# VIA_MOTORS.net
KiCad netlist of a schematic drawn in Altium Designer
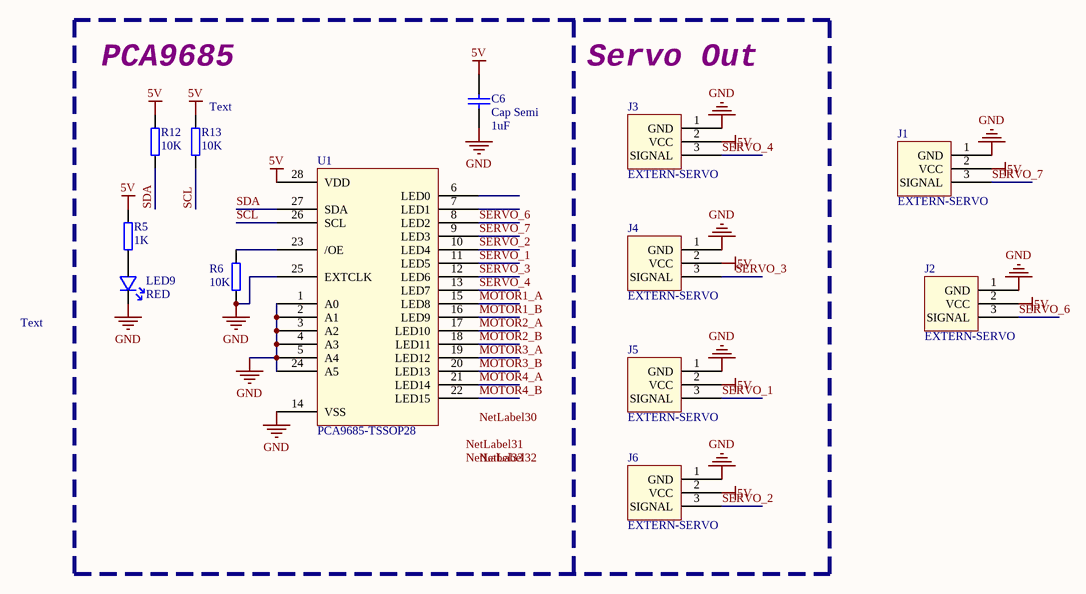
[diagram p0: VIA_MOTORS.SchDoc]

(export (version "E")
  (design (tool "Eeschema 10.0.6"))
  (components
    (comp (ref "C6")
      (value "Cap Semi")
      (footprint "SMT0603")
      (description "CAP SM 0603 X7R 1uF 10%")
      (fields (field (name "TOLERANCE") "±10%") (field (name "ALTIUM_VALUE") "1uF"))
      (libsource (lib "electronpowered") (part "CAP-SM-0603-X7R-1uF"))
    )
    (comp (ref "J1")
      (value "EXTERN-SERVO")
      (footprint "JP3H")
      (libsource (lib "RASHBERRY_EXTERN") (part "EXTERN-SERVO"))
    )
    (comp (ref "J2")
      (value "EXTERN-SERVO")
      (footprint "JP3H")
      (libsource (lib "RASHBERRY_EXTERN") (part "EXTERN-SERVO"))
    )
    (comp (ref "J3")
      (value "EXTERN-SERVO")
      (footprint "JP3H")
      (libsource (lib "RASHBERRY_EXTERN") (part "EXTERN-SERVO"))
    )
    (comp (ref "J4")
      (value "EXTERN-SERVO")
      (footprint "JP3H")
      (libsource (lib "RASHBERRY_EXTERN") (part "EXTERN-SERVO"))
    )
    (comp (ref "J5")
      (value "EXTERN-SERVO")
      (footprint "JP3H")
      (libsource (lib "RASHBERRY_EXTERN") (part "EXTERN-SERVO"))
    )
    (comp (ref "J6")
      (value "EXTERN-SERVO")
      (footprint "JP3H")
      (libsource (lib "RASHBERRY_EXTERN") (part "EXTERN-SERVO"))
    )
    (comp (ref "LED9")
      (value "RED")
      (footprint "SMT0603P")
      (description "LED SM 0603 RED 1V95 FWD VOLTAGE")
      (libsource (lib "electronpowered") (part "LNJ237W82RA"))
    )
    (comp (ref "R5")
      (value "1K")
      (footprint "SMT0603")
      (description "RES SM 0603 1K")
      (fields (field (name "Comment") "Resistor"))
      (libsource (lib "electronpowered") (part "RES-SM-0603-1K"))
    )
    (comp (ref "R6")
      (value "10K")
      (footprint "SMT0603")
      (description "RES SM 0603 10K")
      (fields (field (name "Comment") "Resistor"))
      (libsource (lib "electronpowered") (part "RES-SM-0603-10K"))
    )
    (comp (ref "R12")
      (value "10K")
      (footprint "SMT0603")
      (description "RES SM 0603 10K")
      (fields (field (name "Comment") "Resistor"))
      (libsource (lib "electronpowered") (part "RES-SM-0603-10K"))
    )
    (comp (ref "R13")
      (value "10K")
      (footprint "SMT0603")
      (description "RES SM 0603 10K")
      (fields (field (name "Comment") "Resistor"))
      (libsource (lib "electronpowered") (part "RES-SM-0603-10K"))
    )
    (comp (ref "U1")
      (value "PCA9685-TSSOP28")
      (footprint "TSSOP28-SMD")
      (libsource (lib "RASHBERRY_EXTERN") (part "PCA9685-TSSOP28"))
    )
  )
  (nets
    (net (code "1") (name "/MOTOR1_A") (class "Default")
      (node (ref "U1") (pin "15") (pinfunction "LED8_15") (pintype "passive"))
    )
    (net (code "2") (name "/MOTOR1_B") (class "Default")
      (node (ref "U1") (pin "16") (pinfunction "LED9_16") (pintype "passive"))
    )
    (net (code "3") (name "/MOTOR2_A") (class "Default")
      (node (ref "U1") (pin "17") (pinfunction "LED10_17") (pintype "passive"))
    )
    (net (code "4") (name "/MOTOR2_B") (class "Default")
      (node (ref "U1") (pin "18") (pinfunction "LED11_18") (pintype "passive"))
    )
    (net (code "5") (name "/MOTOR3_A") (class "Default")
      (node (ref "U1") (pin "19") (pinfunction "LED12_19") (pintype "passive"))
    )
    (net (code "6") (name "/MOTOR3_B") (class "Default")
      (node (ref "U1") (pin "20") (pinfunction "LED13_20") (pintype "passive"))
    )
    (net (code "7") (name "/MOTOR4_A") (class "Default")
      (node (ref "U1") (pin "21") (pinfunction "LED14_21") (pintype "passive"))
    )
    (net (code "8") (name "/MOTOR4_B") (class "Default")
      (node (ref "U1") (pin "22") (pinfunction "LED15_22") (pintype "passive"))
    )
    (net (code "13") (name "/SCL") (class "Default")
      (node (ref "R13") (pin "1") (pinfunction "1_1") (pintype "passive"))
      (node (ref "U1") (pin "26") (pinfunction "SCL_26") (pintype "passive"))
    )
    (net (code "14") (name "/SDA") (class "Default")
      (node (ref "R12") (pin "1") (pinfunction "1_1") (pintype "passive"))
      (node (ref "U1") (pin "27") (pinfunction "SDA_27") (pintype "passive"))
    )
    (net (code "15") (name "/SERVO_1") (class "Default")
      (node (ref "J5") (pin "3") (pinfunction "SIGNAL_3") (pintype "passive"))
      (node (ref "U1") (pin "11") (pinfunction "LED5_11") (pintype "passive"))
    )
    (net (code "16") (name "/SERVO_2") (class "Default")
      (node (ref "J6") (pin "3") (pinfunction "SIGNAL_3") (pintype "passive"))
      (node (ref "U1") (pin "10") (pinfunction "LED4_10") (pintype "passive"))
    )
    (net (code "17") (name "/SERVO_3") (class "Default")
      (node (ref "J4") (pin "3") (pinfunction "SIGNAL_3") (pintype "passive"))
      (node (ref "U1") (pin "12") (pinfunction "LED6_12") (pintype "passive"))
    )
    (net (code "18") (name "/SERVO_4") (class "Default")
      (node (ref "J3") (pin "3") (pinfunction "SIGNAL_3") (pintype "passive"))
      (node (ref "U1") (pin "13") (pinfunction "LED7_13") (pintype "passive"))
    )
    (net (code "19") (name "/SERVO_6") (class "Default")
      (node (ref "J2") (pin "3") (pinfunction "SIGNAL_3") (pintype "passive"))
      (node (ref "U1") (pin "8") (pinfunction "LED2_8") (pintype "passive"))
    )
    (net (code "20") (name "/SERVO_7") (class "Default")
      (node (ref "J1") (pin "3") (pinfunction "SIGNAL_3") (pintype "passive"))
      (node (ref "U1") (pin "9") (pinfunction "LED3_9") (pintype "passive"))
    )
    (net (code "21") (name "5V") (class "Default")
      (node (ref "C6") (pin "2") (pinfunction "2_2") (pintype "passive"))
      (node (ref "J1") (pin "2") (pinfunction "VCC_2") (pintype "passive"))
      (node (ref "J2") (pin "2") (pinfunction "VCC_2") (pintype "passive"))
      (node (ref "J3") (pin "2") (pinfunction "VCC_2") (pintype "passive"))
      (node (ref "J4") (pin "2") (pinfunction "VCC_2") (pintype "passive"))
      (node (ref "J5") (pin "2") (pinfunction "VCC_2") (pintype "passive"))
      (node (ref "J6") (pin "2") (pinfunction "VCC_2") (pintype "passive"))
      (node (ref "R12") (pin "2") (pinfunction "2_2") (pintype "passive"))
      (node (ref "R13") (pin "2") (pinfunction "2_2") (pintype "passive"))
      (node (ref "R5") (pin "2") (pinfunction "2_2") (pintype "passive"))
      (node (ref "U1") (pin "28") (pinfunction "VDD_28") (pintype "passive"))
    )
    (net (code "22") (name "GND") (class "Default")
      (node (ref "C6") (pin "1") (pinfunction "1_1") (pintype "passive"))
      (node (ref "J1") (pin "1") (pinfunction "GND_1") (pintype "passive"))
      (node (ref "J2") (pin "1") (pinfunction "GND_1") (pintype "passive"))
      (node (ref "J3") (pin "1") (pinfunction "GND_1") (pintype "passive"))
      (node (ref "J4") (pin "1") (pinfunction "GND_1") (pintype "passive"))
      (node (ref "J5") (pin "1") (pinfunction "GND_1") (pintype "passive"))
      (node (ref "J6") (pin "1") (pinfunction "GND_1") (pintype "passive"))
      (node (ref "LED9") (pin "2") (pinfunction "2_2") (pintype "passive"))
      (node (ref "R6") (pin "1") (pinfunction "1_1") (pintype "passive"))
      (node (ref "U1") (pin "1") (pinfunction "A0_1") (pintype "passive"))
      (node (ref "U1") (pin "14") (pinfunction "VSS_14") (pintype "passive"))
      (node (ref "U1") (pin "2") (pinfunction "A1_2") (pintype "passive"))
      (node (ref "U1") (pin "24") (pinfunction "A5_24") (pintype "passive"))
      (node (ref "U1") (pin "25") (pinfunction "EXTCLK_25") (pintype "passive"))
      (node (ref "U1") (pin "3") (pinfunction "A2_3") (pintype "passive"))
      (node (ref "U1") (pin "4") (pinfunction "A3_4") (pintype "passive"))
      (node (ref "U1") (pin "5") (pinfunction "A4_5") (pintype "passive"))
    )
    (net (code "23") (name "Net-(LED9-Pad1)") (class "Default")
      (node (ref "LED9") (pin "1") (pinfunction "1_1") (pintype "passive"))
      (node (ref "R5") (pin "1") (pinfunction "1_1") (pintype "passive"))
    )
    (net (code "24") (name "Net-(U1-{slash}OE)") (class "Default")
      (node (ref "R6") (pin "2") (pinfunction "2_2") (pintype "passive"))
      (node (ref "U1") (pin "23") (pinfunction "/OE_23") (pintype "passive"))
    )
    (net (code "25") (name "unconnected-(U1-LED0-Pad6)") (class "Default")
      (node (ref "U1") (pin "6") (pinfunction "LED0_6") (pintype "passive"))
    )
    (net (code "26") (name "unconnected-(U1-LED1-Pad7)") (class "Default")
      (node (ref "U1") (pin "7") (pinfunction "LED1_7") (pintype "passive"))
    )
  )
)
